# PCB1.net
KiCad netlist of a schematic drawn in Altium Designer
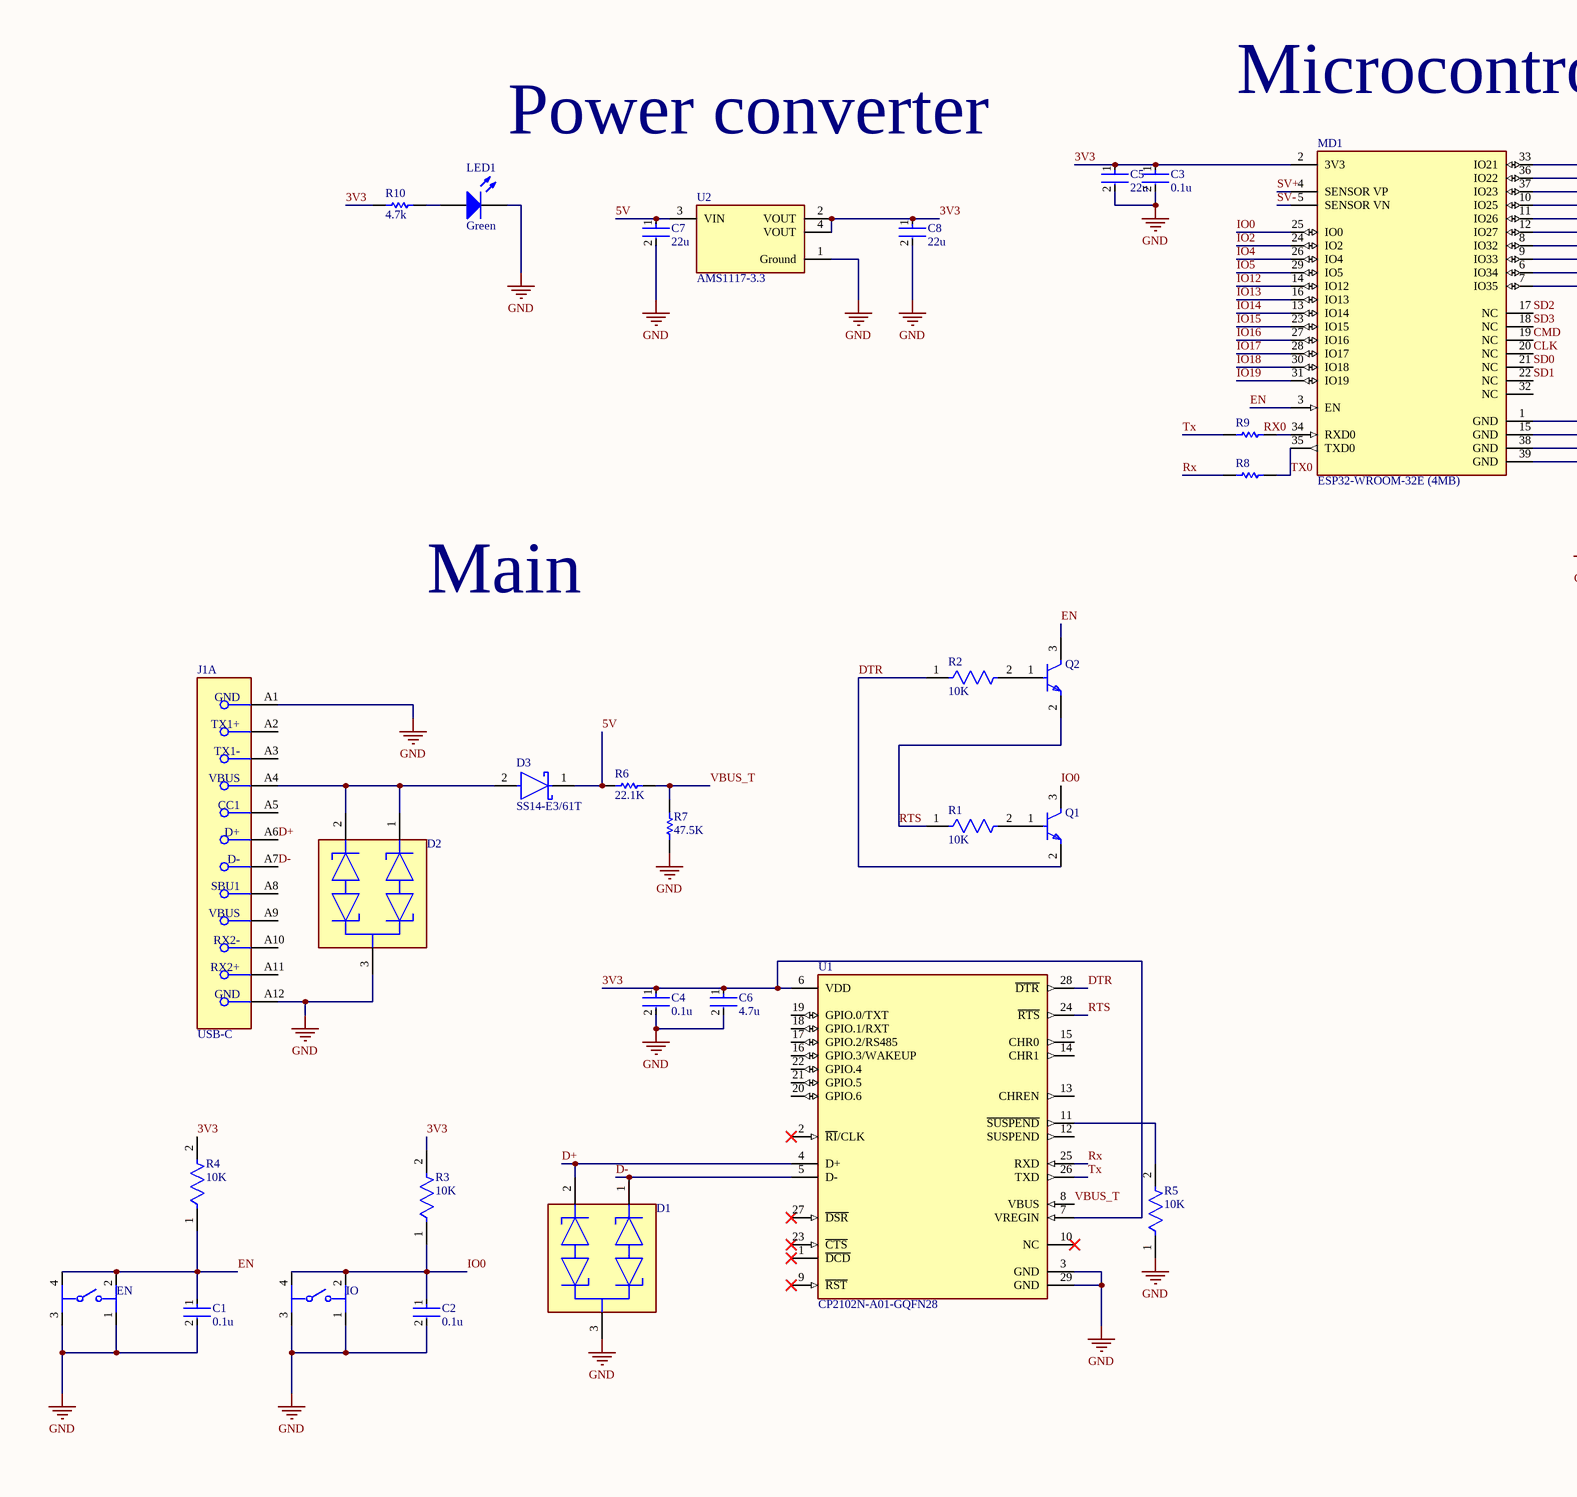
[diagram p0: PCB1.SchDoc, left]
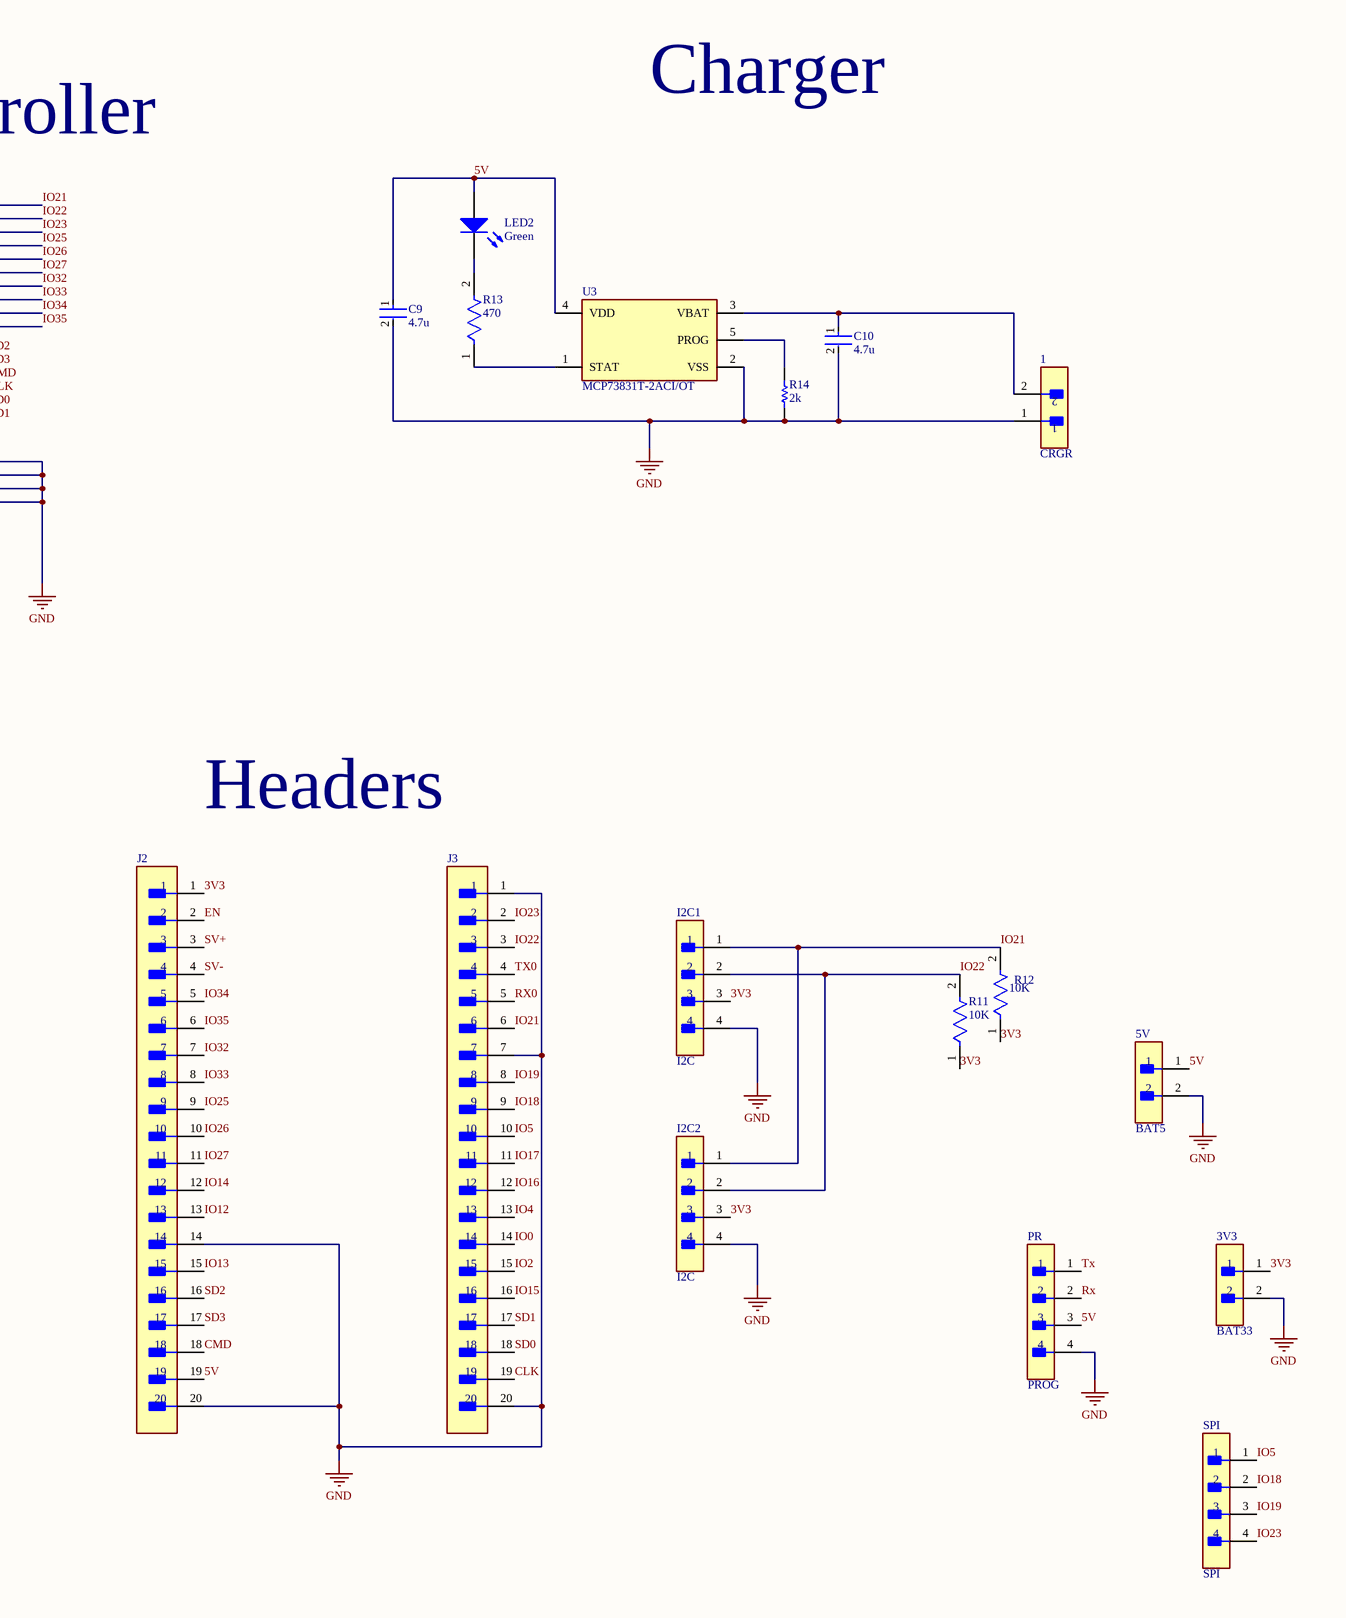
[diagram p1: PCB1.SchDoc, right]

(export (version "E")
  (design (tool "Eeschema 10.0.6"))
  (components
    (comp (ref "1")
      (value "CRGR")
      (footprint "FP-TSW-102-07-F-S-MFG")
      (description "CONN HEADER VERT 2POS 2.54MM")
      (libsource (lib "Altium Content Vault") (part "3bc925449376181038e59eaffc5286c"))
    )
    (comp (ref "3V3")
      (value "BAT33")
      (footprint "FP-TSW-102-07-F-S-MFG")
      (description "CONN HEADER VERT 2POS 2.54MM")
      (libsource (lib "") (part "3bc925449376181038e59eaffc5286c_1"))
    )
    (comp (ref "5V")
      (value "BAT5")
      (footprint "FP-TSW-102-07-F-S-MFG")
      (description "CONN HEADER VERT 2POS 2.54MM")
      (libsource (lib "") (part "3bc925449376181038e59eaffc5286c_1"))
    )
    (comp (ref "C1")
      (value "0.1u")
      (footprint "FP-CGA5L-0_3-0_1-MFG")
      (description "Cap Ceramic 100nF 450V X7T 10% Pad SMD 1206 +125°C Automotive T/R")
      (fields (field (name "TOLERANCE") "10%"))
      (libsource (lib "Altium Content Vault") (part "b4654b650e69147ec39a6b967a45e02"))
    )
    (comp (ref "C2")
      (value "0.1u")
      (footprint "FP-CGA5L-0_3-0_1-MFG")
      (description "Cap Ceramic 100nF 450V X7T 10% Pad SMD 1206 +125°C Automotive T/R")
      (fields (field (name "TOLERANCE") "10%"))
      (libsource (lib "Altium Content Vault") (part "b4654b650e69147ec39a6b967a45e02"))
    )
    (comp (ref "C3")
      (value "0.1u")
      (footprint "FP-CGA5L-0_3-0_1-MFG")
      (description "Cap Ceramic 100nF 450V X7T 10% Pad SMD 1206 +125°C Automotive T/R")
      (fields (field (name "TOLERANCE") "10%"))
      (libsource (lib "Altium Content Vault") (part "b4654b650e69147ec39a6b967a45e02"))
    )
    (comp (ref "C4")
      (value "0.1u")
      (footprint "FP-CGA5L-0_3-0_1-MFG")
      (description "Cap Ceramic 100nF 450V X7T 10% Pad SMD 1206 +125°C Automotive T/R")
      (fields (field (name "TOLERANCE") "10%"))
      (libsource (lib "Altium Content Vault") (part "b4654b650e69147ec39a6b967a45e02"))
    )
    (comp (ref "C5")
      (value "22u")
      (footprint "FP-C3216-160-0_2-IPC_B")
      (description "Multilayer Ceramic Capacitors 22uF ±20% 25V X5R SMD 1206")
      (fields (field (name "TOLERANCE") "20%"))
      (libsource (lib "Altium Content Vault") (part "11868f565c42a9108669ba33697ecf6"))
    )
    (comp (ref "C6")
      (value "4.7u")
      (footprint "FP-CGA5L-0_3-0_1-IPC_B")
      (description "Cap Ceramic 4.7uF 35V X7R 10% Pad SMD 1206 +125°C Automotive T/R")
      (fields (field (name "TOLERANCE") "10%"))
      (libsource (lib "Altium Content Vault") (part "b4654b650e69147ec39a6b967a45e02"))
    )
    (comp (ref "C7")
      (value "22u")
      (footprint "FP-C3216-160-0_2-IPC_B")
      (description "Multilayer Ceramic Capacitors 22uF ±20% 25V X5R SMD 1206")
      (fields (field (name "TOLERANCE") "20%"))
      (libsource (lib "Altium Content Vault") (part "11868f565c42a9108669ba33697ecf6"))
    )
    (comp (ref "C8")
      (value "22u")
      (footprint "FP-C3216-160-0_2-IPC_B")
      (description "Multilayer Ceramic Capacitors 22uF ±20% 25V X5R SMD 1206")
      (fields (field (name "TOLERANCE") "20%"))
      (libsource (lib "Altium Content Vault") (part "11868f565c42a9108669ba33697ecf6"))
    )
    (comp (ref "C9")
      (value "4.7u")
      (footprint "FP-CGA5L-0_3-0_1-IPC_B")
      (description "Cap Ceramic 4.7uF 35V X7R 10% Pad SMD 1206 +125°C Automotive T/R")
      (fields (field (name "TOLERANCE") "10%"))
      (libsource (lib "Altium Content Vault") (part "b4654b650e69147ec39a6b967a45e02"))
    )
    (comp (ref "C10")
      (value "4.7u")
      (footprint "FP-CGA5L-0_3-0_1-IPC_B")
      (description "Cap Ceramic 4.7uF 35V X7R 10% Pad SMD 1206 +125°C Automotive T/R")
      (fields (field (name "TOLERANCE") "10%"))
      (libsource (lib "Altium Content Vault") (part "b4654b650e69147ec39a6b967a45e02"))
    )
    (comp (ref "D1")
      (value "PESD1CAN-UX")
      (footprint "FP-SOT323-MFG")
      (description "TVS DIODE 24V 50V SC70-3")
      (libsource (lib "Altium Content Vault") (part "04d57993b6b7b0f5b3c95ba4f97dea0"))
    )
    (comp (ref "D2")
      (value "PESD1CAN-UX")
      (footprint "FP-SOT323-MFG")
      (description "TVS DIODE 24V 50V SC70-3")
      (libsource (lib "Altium Content Vault") (part "04d57993b6b7b0f5b3c95ba4f97dea0"))
    )
    (comp (ref "D3")
      (value "SS14-E3/61T")
      (footprint "FP-95400-MFG")
      (description "DIODE SCHOTTKY 40V 1A DO214AC")
      (fields
        (field (name "OCTOPART") "https://octopart.com/ss14-e3%2F61t-vishay-39552847")
        (field (name "MANUFACTURER") "Vishay")
      )
      (libsource (lib "Altium Content Vault") (part "1d6ec82d83fb6aee721767c19dac4b9"))
    )
    (comp (ref "EN")
      (value "1301.9315.24")
      (footprint "FP-1301_9315_24-MFG")
      (description "SWITCH TACTILE SPST-NO 0.05A 12V")
      (libsource (lib "Altium Content Vault") (part "c0df99d12937e9d2da15afdedf14b17"))
    )
    (comp (ref "I2C1")
      (value "I2C")
      (footprint "FP-MTLW-104-05-G-S-185-MFG")
      (description "CONN HEADER VERT 4POS 2.54MM")
      (libsource (lib "Altium Content Vault") (part "299a8cea1bdcbc3624fe62c390fa72c"))
    )
    (comp (ref "I2C2")
      (value "I2C")
      (footprint "FP-MTLW-104-05-G-S-185-MFG")
      (description "CONN HEADER VERT 4POS 2.54MM")
      (libsource (lib "Altium Content Vault") (part "299a8cea1bdcbc3624fe62c390fa72c"))
    )
    (comp (ref "IO")
      (value "1301.9315.24")
      (footprint "FP-1301_9315_24-MFG")
      (description "SWITCH TACTILE SPST-NO 0.05A 12V")
      (libsource (lib "Altium Content Vault") (part "c0df99d12937e9d2da15afdedf14b17"))
    )
    (comp (ref "J1")
      (value "USB-C")
      (footprint "FP-1054500101-MFG")
      (description "CONN RCP USB3.1 TYPEC 24P SMD RA")
      (fields
        (field (name "MANUFACTURER") "Molex")
        (field (name "OCTOPART") "https://octopart.com/105450-0101-molex-68082325")
      )
      (libsource (lib "Altium Content Vault") (part "9808b19ecaf079fb99eed69f0495cd0"))
    )
    (comp (ref "J2")
      (value "M52-040023V2045")
      (footprint "FP-M52-040023V2045-MFG")
      (description "CONN HEADER VERT 20POS 1.27MM")
      (libsource (lib "Altium Content Vault") (part "fe5080d2b0106897c8c372ff840dfff"))
    )
    (comp (ref "J3")
      (value "M52-040023V2045")
      (footprint "FP-M52-040023V2045-MFG")
      (description "CONN HEADER VERT 20POS 1.27MM")
      (libsource (lib "Altium Content Vault") (part "fe5080d2b0106897c8c372ff840dfff"))
    )
    (comp (ref "LED1")
      (value "Green")
      (footprint "1206_A")
      (description "SMD mono-color Chip LED, WL-SMCW, Bright Green")
      (fields (field (name "PARTNUMBER") "150120VS75000") (field (name "MANUFACTURER") "Wuerth Elektronik"))
      (libsource (lib "Altium Content Vault") (part "WE-LED_K1A2-2"))
    )
    (comp (ref "LED2")
      (value "Green")
      (footprint "1206_A")
      (description "SMD mono-color Chip LED, WL-SMCW, Bright Green")
      (fields (field (name "PARTNUMBER") "150120VS75000") (field (name "MANUFACTURER") "Wuerth Elektronik"))
      (libsource (lib "Altium Content Vault") (part "WE-LED_K1A2-2"))
    )
    (comp (ref "MD1")
      (value "ESP32-WROOM-32E (4MB)")
      (footprint "FP-ESP32-WROOM-32E_4MB-MFG")
      (description "RX TXRX MOD WIFI TRACE ANT SMD")
      (libsource (lib "Altium Content Vault") (part "7f842c3463a9561e2f6f9fdcd687e0f"))
    )
    (comp (ref "PR")
      (value "PROG")
      (footprint "FP-MTLW-104-05-G-S-185-MFG")
      (description "CONN HEADER VERT 4POS 2.54MM")
      (libsource (lib "Altium Content Vault") (part "299a8cea1bdcbc3624fe62c390fa72c"))
    )
    (comp (ref "Q1")
      (value "SS8050-G")
      (footprint "FP-SS8050-G-MFG")
      (description "NPN TRANSISTOR 1.5A 40V SOT-23 R")
      (libsource (lib "Altium Content Vault") (part "2a1388f82443b098dcd57d24ac7632d"))
    )
    (comp (ref "Q2")
      (value "SS8050-G")
      (footprint "FP-SS8050-G-MFG")
      (description "NPN TRANSISTOR 1.5A 40V SOT-23 R")
      (libsource (lib "Altium Content Vault") (part "2a1388f82443b098dcd57d24ac7632d"))
    )
    (comp (ref "R1")
      (value "10K")
      (footprint "FP-AC1206-MFG")
      (description "RES SMD 10K OHM 5% 1/4W 1206")
      (fields
        (field (name "MANUFACTURER PART NUMBER") "AC1206JR-0710KL")
        (field (name "OCTOPART") "https://octopart.com/ac1206jr-0710kl-yageo-30511262")
      )
      (libsource (lib "Altium Content Vault") (part "1029c3af85768c4190bb7ad29bc67b5"))
    )
    (comp (ref "R2")
      (value "10K")
      (footprint "FP-AC1206-MFG")
      (description "RES SMD 10K OHM 5% 1/4W 1206")
      (fields
        (field (name "MANUFACTURER PART NUMBER") "AC1206JR-0710KL")
        (field (name "OCTOPART") "https://octopart.com/ac1206jr-0710kl-yageo-30511262")
      )
      (libsource (lib "Altium Content Vault") (part "1029c3af85768c4190bb7ad29bc67b5"))
    )
    (comp (ref "R3")
      (value "10K")
      (footprint "FP-AC1206-MFG")
      (description "RES SMD 10K OHM 5% 1/4W 1206")
      (fields
        (field (name "MANUFACTURER PART NUMBER") "AC1206JR-0710KL")
        (field (name "OCTOPART") "https://octopart.com/ac1206jr-0710kl-yageo-30511262")
      )
      (libsource (lib "Altium Content Vault") (part "1029c3af85768c4190bb7ad29bc67b5"))
    )
    (comp (ref "R4")
      (value "10K")
      (footprint "FP-AC1206-MFG")
      (description "RES SMD 10K OHM 5% 1/4W 1206")
      (fields
        (field (name "MANUFACTURER PART NUMBER") "AC1206JR-0710KL")
        (field (name "OCTOPART") "https://octopart.com/ac1206jr-0710kl-yageo-30511262")
      )
      (libsource (lib "Altium Content Vault") (part "1029c3af85768c4190bb7ad29bc67b5"))
    )
    (comp (ref "R5")
      (value "10K")
      (footprint "FP-AC1206-MFG")
      (description "RES SMD 10K OHM 5% 1/4W 1206")
      (fields
        (field (name "MANUFACTURER PART NUMBER") "AC1206JR-0710KL")
        (field (name "OCTOPART") "https://octopart.com/ac1206jr-0710kl-yageo-30511262")
      )
      (libsource (lib "Altium Content Vault") (part "1029c3af85768c4190bb7ad29bc67b5"))
    )
    (comp (ref "R6")
      (value "22.1K")
      (footprint "RESC3216X70X50NL05T20")
      (fields (field (name "PART NUMBER") "ERJ-8ENF2212V") (field (name "MANUFACTURER") "Panasonic"))
      (libsource (lib "Altium Content Vault") (part "RES"))
    )
    (comp (ref "R7")
      (value "47.5K")
      (footprint "RESC3116X65X40LL10T20")
      (fields (field (name "MANUFACTURER") "Yageo") (field (name "PART NUMBER") "RC1206FR-0747K5L"))
      (libsource (lib "Altium Content Vault") (part "RES"))
    )
    (comp (ref "R8")
      (value "ERJ-8GEY0R00V")
      (footprint "RESC3216X70X50NL05T20")
      (fields (field (name "MANUFACTURER") "Panasonic"))
      (libsource (lib "Altium Content Vault") (part "RES"))
    )
    (comp (ref "R9")
      (value "ERJ-8GEY0R00V")
      (footprint "RESC3216X70X50NL05T20")
      (fields (field (name "MANUFACTURER") "Panasonic"))
      (libsource (lib "Altium Content Vault") (part "RES"))
    )
    (comp (ref "R10")
      (value "4.7k")
      (footprint "RESC3216X70X50NL05T20")
      (fields (field (name "PART NUMBER") "ERJ8BQF4R7V") (field (name "MANUFACTURER") "Panasonic"))
      (libsource (lib "Altium Content Vault") (part "RES"))
    )
    (comp (ref "R11")
      (value "10K")
      (footprint "FP-AC1206-MFG")
      (description "RES SMD 10K OHM 5% 1/4W 1206")
      (fields
        (field (name "MANUFACTURER PART NUMBER") "AC1206JR-0710KL")
        (field (name "OCTOPART") "https://octopart.com/ac1206jr-0710kl-yageo-30511262")
      )
      (libsource (lib "Altium Content Vault") (part "1029c3af85768c4190bb7ad29bc67b5"))
    )
    (comp (ref "R12")
      (value "10K")
      (footprint "FP-AC1206-MFG")
      (description "RES SMD 10K OHM 5% 1/4W 1206")
      (fields
        (field (name "MANUFACTURER PART NUMBER") "AC1206JR-0710KL")
        (field (name "OCTOPART") "https://octopart.com/ac1206jr-0710kl-yageo-30511262")
      )
      (libsource (lib "Altium Content Vault") (part "1029c3af85768c4190bb7ad29bc67b5"))
    )
    (comp (ref "R13")
      (value "470")
      (footprint "FP-MCR18-IPC_B")
      (description "Thick Film Chip Resistor, 1206, 470Ω, 5%, 200ppm/°C, 0.25W, 200V")
      (fields (field (name "TOLERANCE") "5%"))
      (libsource (lib "Altium Content Vault") (part "1029c3af85768c4190bb7ad29bc67b5"))
    )
    (comp (ref "R14")
      (value "2k")
      (footprint "RESC3216X60X45LL10T20")
      (fields (field (name "MANUFACTURER") "Vishay Dale") (field (name "PART NUMBER") "CRCW12062K00FKTA"))
      (libsource (lib "Altium Content Vault") (part "RES"))
    )
    (comp (ref "SPI")
      (value "SPI")
      (footprint "FP-MTLW-104-05-G-S-185-MFG")
      (description "CONN HEADER VERT 4POS 2.54MM")
      (libsource (lib "Altium Content Vault") (part "299a8cea1bdcbc3624fe62c390fa72c"))
    )
    (comp (ref "U1")
      (value "CP2102N-A01-GQFN28")
      (footprint "FP-CP2102N-A01-GQFN28-MFG")
      (description "IC BRIDGE USB TO UART 28QFN")
      (fields
        (field (name "MANUFACTURER") "Silicon Labs")
        (field (name "OCTOPART") "https://octopart.com/cp2102n-a01-gqfn28-silicon+labs-74636024")
      )
      (libsource (lib "Altium Content Vault") (part "9ca185fe47a6ee51fa7191d999467af"))
    )
    (comp (ref "U2")
      (value "AMS1117-3.3")
      (footprint "FP-AMS1117-IPC_C")
      (description "LDO Voltage Regulators 1A, 3.3V")
      (fields
        (field (name "OCTOPART") "https://octopart.com/ams1117-3.3-advanced+monolithic+systems-25899300")
        (field (name "MANUFACTURER") "Advanced Monolithic Systems")
      )
      (libsource (lib "Altium Content Vault") (part "8bdbb5f8e77002000e30dd2845d0354"))
    )
    (comp (ref "U3")
      (value "MCP73831T-2ACI/OT")
      (footprint "FP-C04-091-OT-IPC_B")
      (description "IC CONTROLLR LI-ION 4.2V SOT23-5")
      (libsource (lib "Altium Content Vault") (part "61f5a3bb3429d9e0caadea342aa3b19"))
    )
  )
  (nets
    (net (code "1") (name "/3V3") (class "Default")
      (node (ref "3V3") (pin "1") (pinfunction "1_1") (pintype "passive"))
      (node (ref "C3") (pin "1") (pinfunction "1_1") (pintype "passive"))
      (node (ref "C4") (pin "1") (pinfunction "1_1") (pintype "passive"))
      (node (ref "C5") (pin "1") (pinfunction "1_1") (pintype "passive"))
      (node (ref "C6") (pin "1") (pinfunction "1_1") (pintype "passive"))
      (node (ref "C8") (pin "1") (pinfunction "1_1") (pintype "passive"))
      (node (ref "I2C1") (pin "3") (pinfunction "3_3") (pintype "passive"))
      (node (ref "I2C2") (pin "3") (pinfunction "3_3") (pintype "passive"))
      (node (ref "J2") (pin "1") (pinfunction "1_1") (pintype "passive"))
      (node (ref "MD1") (pin "2") (pinfunction "3V3_2") (pintype "power_in"))
      (node (ref "R10") (pin "1") (pinfunction "1_1") (pintype "passive"))
      (node (ref "R11") (pin "1") (pinfunction "1_1") (pintype "passive"))
      (node (ref "R12") (pin "1") (pinfunction "1_1") (pintype "passive"))
      (node (ref "R3") (pin "2") (pinfunction "2_2") (pintype "passive"))
      (node (ref "R4") (pin "2") (pinfunction "2_2") (pintype "passive"))
      (node (ref "U1") (pin "6") (pinfunction "VDD_6") (pintype "power_in"))
      (node (ref "U1") (pin "7") (pinfunction "VREGIN_7") (pintype "input"))
      (node (ref "U2") (pin "2") (pinfunction "VOUT_2") (pintype "passive"))
      (node (ref "U2") (pin "4") (pinfunction "VOUT_4") (pintype "passive"))
    )
    (net (code "2") (name "/5V") (class "Default")
      (node (ref "5V") (pin "1") (pinfunction "1_1") (pintype "passive"))
      (node (ref "C7") (pin "1") (pinfunction "1_1") (pintype "passive"))
      (node (ref "C9") (pin "1") (pinfunction "1_1") (pintype "passive"))
      (node (ref "D3") (pin "1") (pinfunction "C_1") (pintype "passive"))
      (node (ref "J2") (pin "19") (pinfunction "19_19") (pintype "passive"))
      (node (ref "LED2") (pin "2") (pinfunction "A_2") (pintype "passive"))
      (node (ref "PR") (pin "3") (pinfunction "3_3") (pintype "passive"))
      (node (ref "R6") (pin "1") (pinfunction "1_1") (pintype "passive"))
      (node (ref "U2") (pin "3") (pinfunction "VIN_3") (pintype "power_in"))
      (node (ref "U3") (pin "4") (pinfunction "VDD_4") (pintype "power_in"))
    )
    (net (code "3") (name "/CLK") (class "Default")
      (node (ref "J3") (pin "19") (pinfunction "19_19") (pintype "passive"))
      (node (ref "MD1") (pin "20") (pinfunction "NC_20") (pintype "passive"))
    )
    (net (code "4") (name "/CMD") (class "Default")
      (node (ref "J2") (pin "18") (pinfunction "18_18") (pintype "passive"))
      (node (ref "MD1") (pin "19") (pinfunction "NC_19") (pintype "passive"))
    )
    (net (code "5") (name "/D+") (class "Default")
      (node (ref "D1") (pin "2") (pinfunction "cathode_2_2") (pintype "passive"))
      (node (ref "J1") (pin "A6") (pinfunction "D+_A6") (pintype "passive"))
      (node (ref "U1") (pin "4") (pinfunction "D+_4") (pintype "passive"))
    )
    (net (code "6") (name "/D-") (class "Default")
      (node (ref "D1") (pin "1") (pinfunction "cathode_1_1") (pintype "passive"))
      (node (ref "J1") (pin "A7") (pinfunction "D-_A7") (pintype "passive"))
      (node (ref "U1") (pin "5") (pinfunction "D-_5") (pintype "passive"))
    )
    (net (code "7") (name "/DTR") (class "Default")
      (node (ref "Q1") (pin "2") (pinfunction "E_2") (pintype "passive"))
      (node (ref "R2") (pin "1") (pinfunction "1_1") (pintype "passive"))
      (node (ref "U1") (pin "28") (pinfunction "~{DTR}_28") (pintype "output"))
    )
    (net (code "8") (name "/EN") (class "Default")
      (node (ref "C1") (pin "1") (pinfunction "1_1") (pintype "passive"))
      (node (ref "EN") (pin "2") (pinfunction "2_2") (pintype "passive"))
      (node (ref "EN") (pin "4") (pinfunction "4_4") (pintype "passive"))
      (node (ref "J2") (pin "2") (pinfunction "2_2") (pintype "passive"))
      (node (ref "MD1") (pin "3") (pinfunction "EN_3") (pintype "input"))
      (node (ref "Q2") (pin "3") (pinfunction "C_3") (pintype "passive"))
      (node (ref "R4") (pin "1") (pinfunction "1_1") (pintype "passive"))
    )
    (net (code "9") (name "/IO0") (class "Default")
      (node (ref "C2") (pin "1") (pinfunction "1_1") (pintype "passive"))
      (node (ref "IO") (pin "2") (pinfunction "2_2") (pintype "passive"))
      (node (ref "IO") (pin "4") (pinfunction "4_4") (pintype "passive"))
      (node (ref "J3") (pin "14") (pinfunction "14_14") (pintype "passive"))
      (node (ref "MD1") (pin "25") (pinfunction "IO0_25") (pintype "bidirectional"))
      (node (ref "Q1") (pin "3") (pinfunction "C_3") (pintype "passive"))
      (node (ref "R3") (pin "1") (pinfunction "1_1") (pintype "passive"))
    )
    (net (code "10") (name "/IO2") (class "Default")
      (node (ref "J3") (pin "15") (pinfunction "15_15") (pintype "passive"))
      (node (ref "MD1") (pin "24") (pinfunction "IO2_24") (pintype "bidirectional"))
    )
    (net (code "11") (name "/IO4") (class "Default")
      (node (ref "J3") (pin "13") (pinfunction "13_13") (pintype "passive"))
      (node (ref "MD1") (pin "26") (pinfunction "IO4_26") (pintype "bidirectional"))
    )
    (net (code "12") (name "/IO5") (class "Default")
      (node (ref "J3") (pin "10") (pinfunction "10_10") (pintype "passive"))
      (node (ref "MD1") (pin "29") (pinfunction "IO5_29") (pintype "bidirectional"))
      (node (ref "SPI") (pin "1") (pinfunction "1_1") (pintype "passive"))
    )
    (net (code "13") (name "/IO12") (class "Default")
      (node (ref "J2") (pin "13") (pinfunction "13_13") (pintype "passive"))
      (node (ref "MD1") (pin "14") (pinfunction "IO12_14") (pintype "bidirectional"))
    )
    (net (code "14") (name "/IO13") (class "Default")
      (node (ref "J2") (pin "15") (pinfunction "15_15") (pintype "passive"))
      (node (ref "MD1") (pin "16") (pinfunction "IO13_16") (pintype "bidirectional"))
    )
    (net (code "15") (name "/IO14") (class "Default")
      (node (ref "J2") (pin "12") (pinfunction "12_12") (pintype "passive"))
      (node (ref "MD1") (pin "13") (pinfunction "IO14_13") (pintype "bidirectional"))
    )
    (net (code "16") (name "/IO15") (class "Default")
      (node (ref "J3") (pin "16") (pinfunction "16_16") (pintype "passive"))
      (node (ref "MD1") (pin "23") (pinfunction "IO15_23") (pintype "bidirectional"))
    )
    (net (code "17") (name "/IO16") (class "Default")
      (node (ref "J3") (pin "12") (pinfunction "12_12") (pintype "passive"))
      (node (ref "MD1") (pin "27") (pinfunction "IO16_27") (pintype "bidirectional"))
    )
    (net (code "18") (name "/IO17") (class "Default")
      (node (ref "J3") (pin "11") (pinfunction "11_11") (pintype "passive"))
      (node (ref "MD1") (pin "28") (pinfunction "IO17_28") (pintype "bidirectional"))
    )
    (net (code "19") (name "/IO18") (class "Default")
      (node (ref "J3") (pin "9") (pinfunction "9_9") (pintype "passive"))
      (node (ref "MD1") (pin "30") (pinfunction "IO18_30") (pintype "bidirectional"))
      (node (ref "SPI") (pin "2") (pinfunction "2_2") (pintype "passive"))
    )
    (net (code "20") (name "/IO19") (class "Default")
      (node (ref "J3") (pin "8") (pinfunction "8_8") (pintype "passive"))
      (node (ref "MD1") (pin "31") (pinfunction "IO19_31") (pintype "bidirectional"))
      (node (ref "SPI") (pin "3") (pinfunction "3_3") (pintype "passive"))
    )
    (net (code "21") (name "/IO21") (class "Default")
      (node (ref "I2C1") (pin "1") (pinfunction "1_1") (pintype "passive"))
      (node (ref "I2C2") (pin "1") (pinfunction "1_1") (pintype "passive"))
      (node (ref "J3") (pin "6") (pinfunction "6_6") (pintype "passive"))
      (node (ref "MD1") (pin "33") (pinfunction "IO21_33") (pintype "bidirectional"))
      (node (ref "R12") (pin "2") (pinfunction "2_2") (pintype "passive"))
    )
    (net (code "22") (name "/IO22") (class "Default")
      (node (ref "I2C1") (pin "2") (pinfunction "2_2") (pintype "passive"))
      (node (ref "I2C2") (pin "2") (pinfunction "2_2") (pintype "passive"))
      (node (ref "J3") (pin "3") (pinfunction "3_3") (pintype "passive"))
      (node (ref "MD1") (pin "36") (pinfunction "IO22_36") (pintype "bidirectional"))
      (node (ref "R11") (pin "2") (pinfunction "2_2") (pintype "passive"))
    )
    (net (code "23") (name "/IO23") (class "Default")
      (node (ref "J3") (pin "2") (pinfunction "2_2") (pintype "passive"))
      (node (ref "MD1") (pin "37") (pinfunction "IO23_37") (pintype "bidirectional"))
      (node (ref "SPI") (pin "4") (pinfunction "4_4") (pintype "passive"))
    )
    (net (code "24") (name "/IO25") (class "Default")
      (node (ref "J2") (pin "9") (pinfunction "9_9") (pintype "passive"))
      (node (ref "MD1") (pin "10") (pinfunction "IO25_10") (pintype "bidirectional"))
    )
    (net (code "25") (name "/IO26") (class "Default")
      (node (ref "J2") (pin "10") (pinfunction "10_10") (pintype "passive"))
      (node (ref "MD1") (pin "11") (pinfunction "IO26_11") (pintype "bidirectional"))
    )
    (net (code "26") (name "/IO27") (class "Default")
      (node (ref "J2") (pin "11") (pinfunction "11_11") (pintype "passive"))
      (node (ref "MD1") (pin "12") (pinfunction "IO27_12") (pintype "bidirectional"))
    )
    (net (code "27") (name "/IO32") (class "Default")
      (node (ref "J2") (pin "7") (pinfunction "7_7") (pintype "passive"))
      (node (ref "MD1") (pin "8") (pinfunction "IO32_8") (pintype "bidirectional"))
    )
    (net (code "28") (name "/IO33") (class "Default")
      (node (ref "J2") (pin "8") (pinfunction "8_8") (pintype "passive"))
      (node (ref "MD1") (pin "9") (pinfunction "IO33_9") (pintype "bidirectional"))
    )
    (net (code "29") (name "/IO34") (class "Default")
      (node (ref "J2") (pin "5") (pinfunction "5_5") (pintype "passive"))
      (node (ref "MD1") (pin "6") (pinfunction "IO34_6") (pintype "bidirectional"))
    )
    (net (code "30") (name "/IO35") (class "Default")
      (node (ref "J2") (pin "6") (pinfunction "6_6") (pintype "passive"))
      (node (ref "MD1") (pin "7") (pinfunction "IO35_7") (pintype "bidirectional"))
    )
    (net (code "31") (name "/RTS") (class "Default")
      (node (ref "Q2") (pin "2") (pinfunction "E_2") (pintype "passive"))
      (node (ref "R1") (pin "1") (pinfunction "1_1") (pintype "passive"))
      (node (ref "U1") (pin "24") (pinfunction "~{RTS}_24") (pintype "output"))
    )
    (net (code "32") (name "/RX0") (class "Default")
      (node (ref "J3") (pin "5") (pinfunction "5_5") (pintype "passive"))
    )
    (net (code "33") (name "/Rx") (class "Default")
      (node (ref "PR") (pin "2") (pinfunction "2_2") (pintype "passive"))
      (node (ref "R8") (pin "1") (pinfunction "1_1") (pintype "passive"))
      (node (ref "U1") (pin "25") (pinfunction "RXD_25") (pintype "input"))
    )
    (net (code "34") (name "/SD0") (class "Default")
      (node (ref "J3") (pin "18") (pinfunction "18_18") (pintype "passive"))
      (node (ref "MD1") (pin "21") (pinfunction "NC_21") (pintype "passive"))
    )
    (net (code "35") (name "/SD1") (class "Default")
      (node (ref "J3") (pin "17") (pinfunction "17_17") (pintype "passive"))
      (node (ref "MD1") (pin "22") (pinfunction "NC_22") (pintype "passive"))
    )
    (net (code "36") (name "/SD2") (class "Default")
      (node (ref "J2") (pin "16") (pinfunction "16_16") (pintype "passive"))
      (node (ref "MD1") (pin "17") (pinfunction "NC_17") (pintype "passive"))
    )
    (net (code "37") (name "/SD3") (class "Default")
      (node (ref "J2") (pin "17") (pinfunction "17_17") (pintype "passive"))
      (node (ref "MD1") (pin "18") (pinfunction "NC_18") (pintype "passive"))
    )
    (net (code "38") (name "/SV+") (class "Default")
      (node (ref "J2") (pin "3") (pinfunction "3_3") (pintype "passive"))
      (node (ref "MD1") (pin "4") (pinfunction "SENSOR_VP_4") (pintype "passive"))
    )
    (net (code "39") (name "/SV-") (class "Default")
      (node (ref "J2") (pin "4") (pinfunction "4_4") (pintype "passive"))
      (node (ref "MD1") (pin "5") (pinfunction "SENSOR_VN_5") (pintype "passive"))
    )
    (net (code "40") (name "/TX0") (class "Default")
      (node (ref "J3") (pin "4") (pinfunction "4_4") (pintype "passive"))
      (node (ref "MD1") (pin "35") (pinfunction "TXD0_35") (pintype "output"))
      (node (ref "R8") (pin "2") (pinfunction "2_2") (pintype "passive"))
    )
    (net (code "41") (name "/Tx") (class "Default")
      (node (ref "PR") (pin "1") (pinfunction "1_1") (pintype "passive"))
      (node (ref "R9") (pin "1") (pinfunction "1_1") (pintype "passive"))
      (node (ref "U1") (pin "26") (pinfunction "TXD_26") (pintype "output"))
    )
    (net (code "42") (name "/VBUS_T") (class "Default")
      (node (ref "R6") (pin "2") (pinfunction "2_2") (pintype "passive"))
      (node (ref "R7") (pin "2") (pinfunction "2_2") (pintype "passive"))
      (node (ref "U1") (pin "8") (pinfunction "VBUS_8") (pintype "input"))
    )
    (net (code "43") (name "GND") (class "Default")
      (node (ref "1") (pin "1") (pinfunction "1_1") (pintype "passive"))
      (node (ref "3V3") (pin "2") (pinfunction "2_2") (pintype "passive"))
      (node (ref "5V") (pin "2") (pinfunction "2_2") (pintype "passive"))
      (node (ref "C1") (pin "2") (pinfunction "2_2") (pintype "passive"))
      (node (ref "C10") (pin "2") (pinfunction "2_2") (pintype "passive"))
      (node (ref "C2") (pin "2") (pinfunction "2_2") (pintype "passive"))
      (node (ref "C3") (pin "2") (pinfunction "2_2") (pintype "passive"))
      (node (ref "C4") (pin "2") (pinfunction "2_2") (pintype "passive"))
      (node (ref "C5") (pin "2") (pinfunction "2_2") (pintype "passive"))
      (node (ref "C6") (pin "2") (pinfunction "2_2") (pintype "passive"))
      (node (ref "C7") (pin "2") (pinfunction "2_2") (pintype "passive"))
      (node (ref "C8") (pin "2") (pinfunction "2_2") (pintype "passive"))
      (node (ref "C9") (pin "2") (pinfunction "2_2") (pintype "passive"))
      (node (ref "D1") (pin "3") (pinfunction "common_cathode_3") (pintype "passive"))
      (node (ref "D2") (pin "3") (pinfunction "common_cathode_3") (pintype "passive"))
      (node (ref "EN") (pin "1") (pinfunction "1_1") (pintype "passive"))
      (node (ref "EN") (pin "3") (pinfunction "3_3") (pintype "passive"))
      (node (ref "I2C1") (pin "4") (pinfunction "4_4") (pintype "passive"))
      (node (ref "I2C2") (pin "4") (pinfunction "4_4") (pintype "passive"))
      (node (ref "IO") (pin "1") (pinfunction "1_1") (pintype "passive"))
      (node (ref "IO") (pin "3") (pinfunction "3_3") (pintype "passive"))
      (node (ref "J1") (pin "A1") (pinfunction "GND_A1") (pintype "passive"))
      (node (ref "J1") (pin "A12") (pinfunction "GND_A12") (pintype "passive"))
      (node (ref "J2") (pin "14") (pinfunction "14_14") (pintype "passive"))
      (node (ref "J2") (pin "20") (pinfunction "20_20") (pintype "passive"))
      (node (ref "J3") (pin "1") (pinfunction "1_1") (pintype "passive"))
      (node (ref "J3") (pin "20") (pinfunction "20_20") (pintype "passive"))
      (node (ref "J3") (pin "7") (pinfunction "7_7") (pintype "passive"))
      (node (ref "LED1") (pin "1") (pinfunction "K_1") (pintype "passive"))
      (node (ref "MD1") (pin "1") (pinfunction "GND_1") (pintype "power_in"))
      (node (ref "MD1") (pin "15") (pinfunction "GND_15") (pintype "power_in"))
      (node (ref "MD1") (pin "38") (pinfunction "GND_38") (pintype "power_in"))
      (node (ref "MD1") (pin "39") (pinfunction "GND_39") (pintype "power_in"))
      (node (ref "PR") (pin "4") (pinfunction "4_4") (pintype "passive"))
      (node (ref "R14") (pin "1") (pinfunction "1_1") (pintype "passive"))
      (node (ref "R5") (pin "1") (pinfunction "1_1") (pintype "passive"))
      (node (ref "R7") (pin "1") (pinfunction "1_1") (pintype "passive"))
      (node (ref "U1") (pin "29") (pinfunction "GND_29") (pintype "power_in"))
      (node (ref "U1") (pin "3") (pinfunction "GND_3") (pintype "power_in"))
      (node (ref "U2") (pin "1") (pinfunction "Ground_1") (pintype "power_in"))
      (node (ref "U3") (pin "2") (pinfunction "VSS_2") (pintype "power_in"))
    )
    (net (code "44") (name "Net-(D2-cathode_1)") (class "Default")
      (node (ref "D2") (pin "1") (pinfunction "cathode_1_1") (pintype "passive"))
      (node (ref "D2") (pin "2") (pinfunction "cathode_2_2") (pintype "passive"))
      (node (ref "D3") (pin "2") (pinfunction "A_2") (pintype "passive"))
      (node (ref "J1") (pin "A4") (pinfunction "VBUS_A4") (pintype "passive"))
    )
    (net (code "45") (name "Net-(LED1-A)") (class "Default")
      (node (ref "LED1") (pin "2") (pinfunction "A_2") (pintype "passive"))
      (node (ref "R10") (pin "2") (pinfunction "2_2") (pintype "passive"))
    )
    (net (code "46") (name "Net-(LED2-K)") (class "Default")
      (node (ref "LED2") (pin "1") (pinfunction "K_1") (pintype "passive"))
      (node (ref "R13") (pin "2") (pinfunction "2_2") (pintype "passive"))
    )
    (net (code "47") (name "Net-(MD1-RXD0)") (class "Default")
      (node (ref "MD1") (pin "34") (pinfunction "RXD0_34") (pintype "input"))
      (node (ref "R9") (pin "2") (pinfunction "2_2") (pintype "passive"))
    )
    (net (code "48") (name "Net-(Q1-B)") (class "Default")
      (node (ref "Q1") (pin "1") (pinfunction "B_1") (pintype "passive"))
      (node (ref "R1") (pin "2") (pinfunction "2_2") (pintype "passive"))
    )
    (net (code "49") (name "Net-(Q2-B)") (class "Default")
      (node (ref "Q2") (pin "1") (pinfunction "B_1") (pintype "passive"))
      (node (ref "R2") (pin "2") (pinfunction "2_2") (pintype "passive"))
    )
    (net (code "50") (name "Net-(U1-~{SUSPEND})") (class "Default")
      (node (ref "R5") (pin "2") (pinfunction "2_2") (pintype "passive"))
      (node (ref "U1") (pin "11") (pinfunction "~{SUSPEND}_11") (pintype "output"))
    )
    (net (code "51") (name "Net-(U3-PROG)") (class "Default")
      (node (ref "R14") (pin "2") (pinfunction "2_2") (pintype "passive"))
      (node (ref "U3") (pin "5") (pinfunction "PROG_5") (pintype "passive"))
    )
    (net (code "52") (name "Net-(U3-STAT)") (class "Default")
      (node (ref "R13") (pin "1") (pinfunction "1_1") (pintype "passive"))
      (node (ref "U3") (pin "1") (pinfunction "STAT_1") (pintype "passive"))
    )
    (net (code "53") (name "Net-(U3-VBAT)") (class "Default")
      (node (ref "1") (pin "2") (pinfunction "2_2") (pintype "passive"))
      (node (ref "C10") (pin "1") (pinfunction "1_1") (pintype "passive"))
      (node (ref "U3") (pin "3") (pinfunction "VBAT_3") (pintype "power_in"))
    )
    (net (code "54") (name "unconnected-(J1A-CC1-PadA5)") (class "Default")
      (node (ref "J1") (pin "A5") (pinfunction "CC1_A5") (pintype "passive"))
    )
    (net (code "55") (name "unconnected-(J1A-RX2+-PadA11)") (class "Default")
      (node (ref "J1") (pin "A11") (pinfunction "RX2+_A11") (pintype "passive"))
    )
    (net (code "56") (name "unconnected-(J1A-RX2--PadA10)") (class "Default")
      (node (ref "J1") (pin "A10") (pinfunction "RX2-_A10") (pintype "passive"))
    )
    (net (code "57") (name "unconnected-(J1A-SBU1-PadA8)") (class "Default")
      (node (ref "J1") (pin "A8") (pinfunction "SBU1_A8") (pintype "passive"))
    )
    (net (code "58") (name "unconnected-(J1A-TX1+-PadA2)") (class "Default")
      (node (ref "J1") (pin "A2") (pinfunction "TX1+_A2") (pintype "passive"))
    )
    (net (code "59") (name "unconnected-(J1A-TX1--PadA3)") (class "Default")
      (node (ref "J1") (pin "A3") (pinfunction "TX1-_A3") (pintype "passive"))
    )
    (net (code "60") (name "unconnected-(J1A-VBUS-PadA9)") (class "Default")
      (node (ref "J1") (pin "A9") (pinfunction "VBUS_A9") (pintype "passive"))
    )
    (net (code "61") (name "unconnected-(MD1-NC-Pad32)") (class "Default")
      (node (ref "MD1") (pin "32") (pinfunction "NC_32") (pintype "passive"))
    )
    (net (code "62") (name "unconnected-(U1-CHR0-Pad15)") (class "Default")
      (node (ref "U1") (pin "15") (pinfunction "CHR0_15") (pintype "output"))
    )
    (net (code "63") (name "unconnected-(U1-CHR1-Pad14)") (class "Default")
      (node (ref "U1") (pin "14") (pinfunction "CHR1_14") (pintype "output"))
    )
    (net (code "64") (name "unconnected-(U1-CHREN-Pad13)") (class "Default")
      (node (ref "U1") (pin "13") (pinfunction "CHREN_13") (pintype "output"))
    )
    (net (code "65") (name "unconnected-(U1-GPIO.0{slash}TXT-Pad19)") (class "Default")
      (node (ref "U1") (pin "19") (pinfunction "GPIO.0/TXT_19") (pintype "bidirectional"))
    )
    (net (code "66") (name "unconnected-(U1-GPIO.1{slash}RXT-Pad18)") (class "Default")
      (node (ref "U1") (pin "18") (pinfunction "GPIO.1/RXT_18") (pintype "bidirectional"))
    )
    (net (code "67") (name "unconnected-(U1-GPIO.2{slash}RS485-Pad17)") (class "Default")
      (node (ref "U1") (pin "17") (pinfunction "GPIO.2/RS485_17") (pintype "bidirectional"))
    )
    (net (code "68") (name "unconnected-(U1-GPIO.3{slash}WAKEUP-Pad16)") (class "Default")
      (node (ref "U1") (pin "16") (pinfunction "GPIO.3/WAKEUP_16") (pintype "bidirectional"))
    )
    (net (code "69") (name "unconnected-(U1-GPIO.4-Pad22)") (class "Default")
      (node (ref "U1") (pin "22") (pinfunction "GPIO.4_22") (pintype "bidirectional"))
    )
    (net (code "70") (name "unconnected-(U1-GPIO.5-Pad21)") (class "Default")
      (node (ref "U1") (pin "21") (pinfunction "GPIO.5_21") (pintype "bidirectional"))
    )
    (net (code "71") (name "unconnected-(U1-GPIO.6-Pad20)") (class "Default")
      (node (ref "U1") (pin "20") (pinfunction "GPIO.6_20") (pintype "bidirectional"))
    )
    (net (code "72") (name "unconnected-(U1-NC-Pad10)") (class "Default")
      (node (ref "U1") (pin "10") (pinfunction "NC_10") (pintype "passive+no_connect"))
    )
    (net (code "73") (name "unconnected-(U1-SUSPEND-Pad12)") (class "Default")
      (node (ref "U1") (pin "12") (pinfunction "SUSPEND_12") (pintype "output"))
    )
    (net (code "74") (name "unconnected-(U1-~{CTS}-Pad23)") (class "Default")
      (node (ref "U1") (pin "23") (pinfunction "~{CTS}_23") (pintype "input+no_connect"))
    )
    (net (code "75") (name "unconnected-(U1-~{DCD}-Pad1)") (class "Default")
      (node (ref "U1") (pin "1") (pinfunction "~{DCD}_1") (pintype "passive+no_connect"))
    )
    (net (code "76") (name "unconnected-(U1-~{DSR}-Pad27)") (class "Default")
      (node (ref "U1") (pin "27") (pinfunction "~{DSR}_27") (pintype "input+no_connect"))
    )
    (net (code "77") (name "unconnected-(U1-~{RI}{slash}CLK-Pad2)") (class "Default")
      (node (ref "U1") (pin "2") (pinfunction "~{RI}/CLK_2") (pintype "input+no_connect"))
    )
    (net (code "78") (name "unconnected-(U1-~{RST}-Pad9)") (class "Default")
      (node (ref "U1") (pin "9") (pinfunction "~{RST}_9") (pintype "input+no_connect"))
    )
  )
)
